# Sheet1.net
KiCad netlist of a schematic drawn in Altium Designer
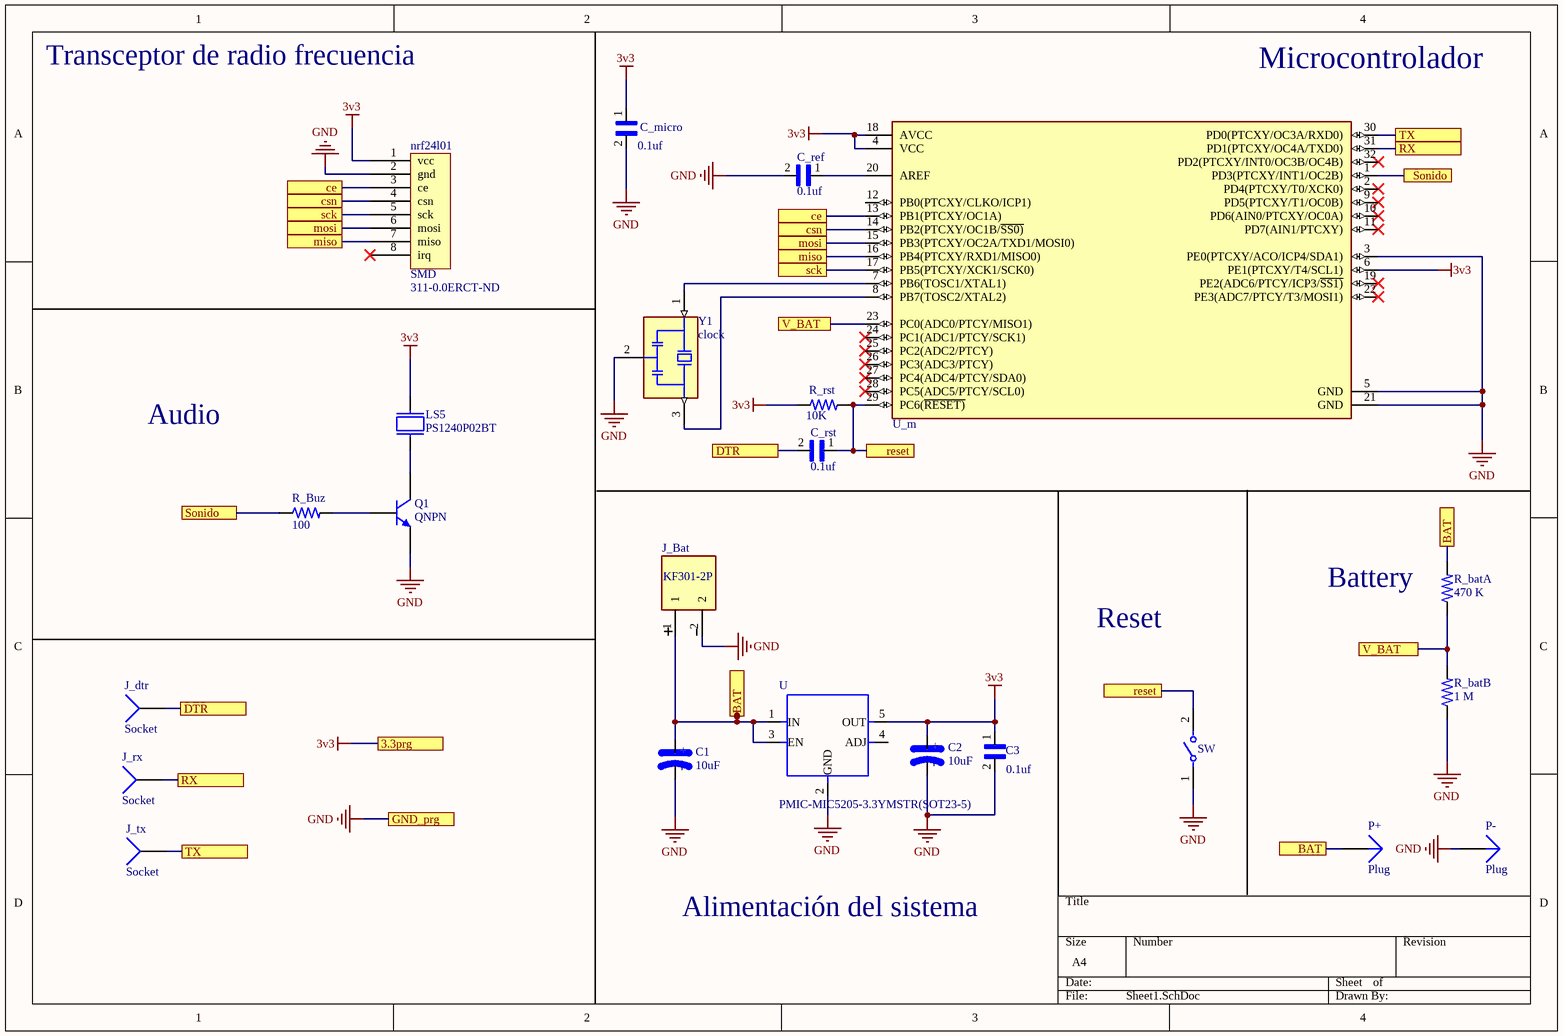
[diagram p0: Sheet1.SchDoc]

(export (version "E")
  (design (tool "Eeschema 10.0.6"))
  (components
    (comp (ref "C1")
      (value "10uF")
      (footprint "CT1206")
      (description "10ÂµF Molded Tantalum Capacitors 20V 1206 _3216 Metric_ 5Ohm")
      (fields (field (name "MF") "KEMET") (field (name "MP") "T491A106M020AT"))
      (libsource (lib "1206_tantalio") (part "TANTALUM-SMD-10UF-20V-20%(1206)"))
    )
    (comp (ref "C2")
      (value "10uF")
      (footprint "CT1206")
      (description "10ÂµF Molded Tantalum Capacitors 20V 1206 _3216 Metric_ 5Ohm")
      (fields (field (name "MF") "KEMET") (field (name "MP") "T491A106M020AT"))
      (libsource (lib "1206_tantalio") (part "TANTALUM-SMD-10UF-20V-20%(1206)"))
    )
    (comp (ref "C3")
      (value "0.1uf")
      (footprint "CAPC1608X90")
      (description "0.1ÂµF Â±10% 50V Ceramic Capacitor X7R 0603 _1608 Metric_")
      (fields (field (name "DIGI-KEY_PART_NUMBER") "311-1344-1-ND") (field (name "MP") "CC0603KRX7R9BB104"))
      (libsource (lib "cap0603") (part "CC0603KRX7R9BB104"))
    )
    (comp (ref "C_micro")
      (value "0.1uf")
      (footprint "CAPC1608X90")
      (description "0.1ÂµF Â±10% 50V Ceramic Capacitor X7R 0603 _1608 Metric_")
      (fields (field (name "DIGI-KEY_PART_NUMBER") "311-1344-1-ND") (field (name "MP") "CC0603KRX7R9BB104"))
      (libsource (lib "cap0603") (part "CC0603KRX7R9BB104"))
    )
    (comp (ref "C_ref")
      (value "0.1uf")
      (footprint "CAPC1608X90")
      (description "0.1ÂµF Â±10% 50V Ceramic Capacitor X7R 0603 _1608 Metric_")
      (fields (field (name "DIGI-KEY_PART_NUMBER") "311-1344-1-ND") (field (name "MP") "CC0603KRX7R9BB104"))
      (libsource (lib "") (part "CC0603KRX7R9BB104_1"))
    )
    (comp (ref "C_rst")
      (value "0.1uf")
      (footprint "CAPC1608X90")
      (description "0.1ÂµF Â±10% 50V Ceramic Capacitor X7R 0603 _1608 Metric_")
      (fields (field (name "DIGI-KEY_PART_NUMBER") "311-1344-1-ND") (field (name "MP") "CC0603KRX7R9BB104"))
      (libsource (lib "") (part "CC0603KRX7R9BB104_1"))
    )
    (comp (ref "J_Bat")
      (value "KF301-2P")
      (footprint "HANDSON_KF301-2P")
      (description "2 Pin Terminal Block 5mm Pitch")
      (fields (field (name "MF") "Handson Technology"))
      (libsource (lib "bornera") (part "KF301-2P"))
    )
    (comp (ref "J_dtr")
      (value "Socket")
      (footprint "PIN1")
      (fields (field (name "PUBLISHER") "Altium Limited"))
      (libsource (lib "Miscellaneous Connectors") (part "Socket"))
    )
    (comp (ref "J_rx")
      (value "Socket")
      (footprint "PIN1")
      (fields (field (name "PUBLISHER") "Altium Limited"))
      (libsource (lib "Miscellaneous Connectors") (part "Socket"))
    )
    (comp (ref "J_tx")
      (value "Socket")
      (footprint "PIN1")
      (fields (field (name "PUBLISHER") "Altium Limited"))
      (libsource (lib "Miscellaneous Connectors") (part "Socket"))
    )
    (comp (ref "LS5")
      (value "PS1240P02BT")
      (footprint "XDCR_PS1240P02BT")
      (description "Buzzers Transducer, Externally Driven Piezo 3V 4kHz 60dB @ 3V, 10cm Through Hole PC Pins")
      (fields (field (name "MF") "TDK"))
      (libsource (lib "buzzerGrande") (part "PS1240P02BT"))
    )
    (comp (ref "nrf24l01")
      (value "SMD")
      (footprint "NRF24L01")
      (fields (field (name "SUPPLIER PART NUMBER 1") "311-0.0ERCT-ND"))
      (libsource (lib "Schlib1") (part "nrf24l01_smd"))
    )
    (comp (ref "P+")
      (value "Plug")
      (footprint "PIN1")
      (fields (field (name "PUBLISHER") "Altium Limited"))
      (libsource (lib "Miscellaneous Connectors") (part "Plug"))
    )
    (comp (ref "P-")
      (value "Plug")
      (footprint "PIN1")
      (fields (field (name "PUBLISHER") "Altium Limited"))
      (libsource (lib "Miscellaneous Connectors") (part "Plug"))
    )
    (comp (ref "Q1")
      (value "QNPN")
      (footprint "SOT-23B_N")
      (description "NPN Bipolar Transistor")
      (fields (field (name "PUBLISHER") "Altium Limited"))
      (libsource (lib "Miscellaneous Devices") (part "QNPN"))
    )
    (comp (ref "R_batA")
      (value "470 K")
      (footprint "RESC2012X65N")
      (description "RES 0.33 OHM 1% 1/4W 0805")
      (fields (field (name "MF") "TE Connectivity") (field (name "TOLERANCE") "1%"))
      (libsource (lib "RES0805") (part "2-2176053-0"))
    )
    (comp (ref "R_batB")
      (value "1 M")
      (footprint "RESC2012X65N")
      (description "RES 0.33 OHM 1% 1/4W 0805")
      (fields (field (name "MF") "TE Connectivity") (field (name "TOLERANCE") "1%"))
      (libsource (lib "RES0805") (part "2-2176053-0"))
    )
    (comp (ref "R_Buz")
      (value "100")
      (footprint "RESC2012X65N")
      (description "RES 0.33 OHM 1% 1/4W 0805")
      (fields (field (name "MF") "TE Connectivity") (field (name "TOLERANCE") "1%"))
      (libsource (lib "RES0805") (part "2-2176053-0"))
    )
    (comp (ref "R_rst")
      (value "10K")
      (footprint "RES0603:RESC1608X50N")
      (description "Res, Thin Film, 13r, 0.1%, 0.1w, 0603")
      (fields (field (name "MP") "RP73D1J13RBTDG") (field (name "MF") "TE Connectivity"))
      (libsource (lib "RES0603") (part "RP73D1J13RBTDG"))
    )
    (comp (ref "SW")
      (value "B3U-1000P-B")
      (footprint "Omron_0_MFG")
      (libsource (lib "Switch_Omron_B3U-1000P-B_eec") (part "B3U-1000P-B"))
    )
    (comp (ref "U")
      (value "PMIC-MIC5205-3.3YMSTR(SOT23-5)")
      (footprint "SOT-23-5")
      (description "Linear Voltage Regulator IC 1 Output 150mA SOT-23-5")
      (fields (field (name "MP") "MIC5205-3.3YM5-TR") (field (name "MF") "Microchip"))
      (libsource (lib "3.3mini") (part "PMIC-MIC5205-3.3YMSTR(SOT23-5)"))
    )
    (comp (ref "U_m")
      (value "ATMEGA328PB-AUR")
      (footprint "Microchip_C04-074_IPC_C")
      (libsource (lib "IC_Microchip_ATMEGA328PB-AUR_eec") (part "ATMEGA328PB-AUR"))
    )
    (comp (ref "Y1")
      (value "clock")
      (footprint "OSC_CSTCE8M00G52-R0")
      (description "8MHz Ceramic Resonator Built in Capacitor 10pF Â±0.2% -20Â°C ~ 80Â°C Surface Mount")
      (fields (field (name "MF") "Murata") (field (name "MP") "CSTCE8M00G52-R0"))
      (libsource (lib "CSTCE8M00G52-R0") (part "CSTCE8M00G52-R0"))
    )
  )
  (nets
    (net (code "1") (name "/BAT") (class "Default")
      (node (ref "C1") (pin "POS") (pinfunction "POS_POS") (pintype "passive"))
      (node (ref "J_Bat") (pin "1") (pinfunction "1_1") (pintype "passive"))
      (node (ref "P+") (pin "1") (pinfunction "1_1") (pintype "passive"))
      (node (ref "R_batA") (pin "2") (pinfunction "2_2") (pintype "passive"))
      (node (ref "U") (pin "1") (pinfunction "IN_1") (pintype "bidirectional"))
      (node (ref "U") (pin "3") (pinfunction "EN_3") (pintype "bidirectional"))
    )
    (net (code "2") (name "/DTR") (class "Default")
      (node (ref "C_rst") (pin "2") (pinfunction "2_2") (pintype "passive"))
      (node (ref "J_dtr") (pin "1") (pinfunction "1_1") (pintype "passive"))
    )
    (net (code "3") (name "/RX") (class "Default")
      (node (ref "J_rx") (pin "1") (pinfunction "1_1") (pintype "passive"))
      (node (ref "U_m") (pin "31") (pinfunction "PD1(PTCXY/OC4A/TXD0)_31") (pintype "bidirectional"))
    )
    (net (code "4") (name "/Sonido") (class "Default")
      (node (ref "R_Buz") (pin "1") (pinfunction "1_1") (pintype "passive"))
      (node (ref "U_m") (pin "1") (pinfunction "PD3(PTCXY/INT1/OC2B)_1") (pintype "bidirectional"))
    )
    (net (code "5") (name "/TX") (class "Default")
      (node (ref "J_tx") (pin "1") (pinfunction "1_1") (pintype "passive"))
      (node (ref "U_m") (pin "30") (pinfunction "PD0(PTCXY/OC3A/RXD0)_30") (pintype "bidirectional"))
    )
    (net (code "6") (name "/V_BAT") (class "Default")
      (node (ref "R_batA") (pin "1") (pinfunction "1_1") (pintype "passive"))
      (node (ref "R_batB") (pin "2") (pinfunction "2_2") (pintype "passive"))
      (node (ref "U_m") (pin "23") (pinfunction "PC0(ADC0/PTCY/MISO1)_23") (pintype "bidirectional"))
    )
    (net (code "7") (name "/ce") (class "Default")
      (node (ref "U_m") (pin "13") (pinfunction "PB1(PTCXY/OC1A)_13") (pintype "bidirectional"))
      (node (ref "nrf24l01") (pin "3") (pinfunction "ce_3") (pintype "passive"))
    )
    (net (code "8") (name "/csn") (class "Default")
      (node (ref "U_m") (pin "14") (pinfunction "PB2(PTCXY/OC1B/~{SS0)}_14") (pintype "bidirectional"))
      (node (ref "nrf24l01") (pin "4") (pinfunction "csn_4") (pintype "passive"))
    )
    (net (code "9") (name "/miso") (class "Default")
      (node (ref "U_m") (pin "16") (pinfunction "PB4(PTCXY/RXD1/MISO0)_16") (pintype "bidirectional"))
      (node (ref "nrf24l01") (pin "7") (pinfunction "miso_7") (pintype "passive"))
    )
    (net (code "10") (name "/mosi") (class "Default")
      (node (ref "U_m") (pin "15") (pinfunction "PB3(PTCXY/OC2A/TXD1/MOSI0)_15") (pintype "bidirectional"))
      (node (ref "nrf24l01") (pin "6") (pinfunction "mosi_6") (pintype "passive"))
    )
    (net (code "11") (name "/reset") (class "Default")
      (node (ref "C_rst") (pin "1") (pinfunction "1_1") (pintype "passive"))
      (node (ref "R_rst") (pin "2") (pinfunction "2_2") (pintype "passive"))
      (node (ref "SW") (pin "2") (pinfunction "2_2") (pintype "passive"))
      (node (ref "U_m") (pin "29") (pinfunction "PC6(~{RESET)}_29") (pintype "bidirectional"))
    )
    (net (code "12") (name "/sck") (class "Default")
      (node (ref "U_m") (pin "17") (pinfunction "PB5(PTCXY/XCK1/SCK0)_17") (pintype "bidirectional"))
      (node (ref "nrf24l01") (pin "5") (pinfunction "sck_5") (pintype "passive"))
    )
    (net (code "13") (name "3v3") (class "Default")
      (node (ref "C2") (pin "POS") (pinfunction "POS_POS") (pintype "passive"))
      (node (ref "C3") (pin "1") (pinfunction "1_1") (pintype "passive"))
      (node (ref "C_micro") (pin "1") (pinfunction "1_1") (pintype "passive"))
      (node (ref "LS5") (pin "1") (pinfunction "1_1") (pintype "passive"))
      (node (ref "R_rst") (pin "1") (pinfunction "1_1") (pintype "passive"))
      (node (ref "U") (pin "5") (pinfunction "OUT_5") (pintype "bidirectional"))
      (node (ref "U_m") (pin "18") (pinfunction "AVCC_18") (pintype "power_in"))
      (node (ref "U_m") (pin "4") (pinfunction "VCC_4") (pintype "power_in"))
      (node (ref "U_m") (pin "6") (pinfunction "PE1(PTCXY/T4/SCL1)_6") (pintype "bidirectional"))
      (node (ref "nrf24l01") (pin "1") (pinfunction "vcc_1") (pintype "passive"))
    )
    (net (code "14") (name "GND") (class "Default")
      (node (ref "C1") (pin "NEG") (pinfunction "NEG_NEG") (pintype "passive"))
      (node (ref "C2") (pin "NEG") (pinfunction "NEG_NEG") (pintype "passive"))
      (node (ref "C3") (pin "2") (pinfunction "2_2") (pintype "passive"))
      (node (ref "C_micro") (pin "2") (pinfunction "2_2") (pintype "passive"))
      (node (ref "C_ref") (pin "2") (pinfunction "2_2") (pintype "passive"))
      (node (ref "J_Bat") (pin "2") (pinfunction "2_2") (pintype "passive"))
      (node (ref "P-") (pin "1") (pinfunction "1_1") (pintype "passive"))
      (node (ref "Q1") (pin "3") (pinfunction "E_3") (pintype "passive"))
      (node (ref "R_batB") (pin "1") (pinfunction "1_1") (pintype "passive"))
      (node (ref "SW") (pin "1") (pinfunction "1_1") (pintype "passive"))
      (node (ref "U") (pin "2") (pinfunction "GND_2") (pintype "bidirectional"))
      (node (ref "U_m") (pin "21") (pinfunction "GND_21") (pintype "power_in"))
      (node (ref "U_m") (pin "3") (pinfunction "PE0(PTCXY/ACO/ICP4/SDA1)_3") (pintype "bidirectional"))
      (node (ref "U_m") (pin "5") (pinfunction "GND_5") (pintype "power_in"))
      (node (ref "Y1") (pin "2") (pinfunction "GND_2") (pintype "power_in"))
      (node (ref "nrf24l01") (pin "2") (pinfunction "gnd_2") (pintype "passive"))
    )
    (net (code "15") (name "Net-(Q1-B)") (class "Default")
      (node (ref "Q1") (pin "2") (pinfunction "B_2") (pintype "passive"))
      (node (ref "R_Buz") (pin "2") (pinfunction "2_2") (pintype "passive"))
    )
    (net (code "16") (name "Net-(Q1-C)") (class "Default")
      (node (ref "LS5") (pin "2") (pinfunction "2_2") (pintype "passive"))
      (node (ref "Q1") (pin "1") (pinfunction "C_1") (pintype "passive"))
    )
    (net (code "17") (name "Net-(U_m-AREF)") (class "Default")
      (node (ref "C_ref") (pin "1") (pinfunction "1_1") (pintype "passive"))
      (node (ref "U_m") (pin "20") (pinfunction "AREF_20") (pintype "power_in"))
    )
    (net (code "18") (name "Net-(U_m-PB6(TOSC1{slash}XTAL1))") (class "Default")
      (node (ref "U_m") (pin "7") (pinfunction "PB6(TOSC1/XTAL1)_7") (pintype "bidirectional"))
      (node (ref "Y1") (pin "1") (pinfunction "IN_1") (pintype "input"))
    )
    (net (code "19") (name "Net-(U_m-PB7(TOSC2{slash}XTAL2))") (class "Default")
      (node (ref "U_m") (pin "8") (pinfunction "PB7(TOSC2/XTAL2)_8") (pintype "bidirectional"))
      (node (ref "Y1") (pin "3") (pinfunction "OUT_3") (pintype "output"))
    )
    (net (code "20") (name "unconnected-(U-ADJ-Pad4)") (class "Default")
      (node (ref "U") (pin "4") (pinfunction "ADJ_4") (pintype "bidirectional"))
    )
    (net (code "21") (name "unconnected-(U_m-PB0(PTCXY{slash}CLKO{slash}ICP1)-Pad12)") (class "Default")
      (node (ref "U_m") (pin "12") (pinfunction "PB0(PTCXY/CLKO/ICP1)_12") (pintype "bidirectional"))
    )
    (net (code "22") (name "unconnected-(U_m-PC1(ADC1{slash}PTCY{slash}SCK1)-Pad24)") (class "Default")
      (node (ref "U_m") (pin "24") (pinfunction "PC1(ADC1/PTCY/SCK1)_24") (pintype "bidirectional+no_connect"))
    )
    (net (code "23") (name "unconnected-(U_m-PC2(ADC2{slash}PTCY)-Pad25)") (class "Default")
      (node (ref "U_m") (pin "25") (pinfunction "PC2(ADC2/PTCY)_25") (pintype "bidirectional+no_connect"))
    )
    (net (code "24") (name "unconnected-(U_m-PC3(ADC3{slash}PTCY)-Pad26)") (class "Default")
      (node (ref "U_m") (pin "26") (pinfunction "PC3(ADC3/PTCY)_26") (pintype "bidirectional+no_connect"))
    )
    (net (code "25") (name "unconnected-(U_m-PC4(ADC4{slash}PTCY{slash}SDA0)-Pad27)") (class "Default")
      (node (ref "U_m") (pin "27") (pinfunction "PC4(ADC4/PTCY/SDA0)_27") (pintype "bidirectional+no_connect"))
    )
    (net (code "26") (name "unconnected-(U_m-PC5(ADC5{slash}PTCY{slash}SCL0)-Pad28)") (class "Default")
      (node (ref "U_m") (pin "28") (pinfunction "PC5(ADC5/PTCY/SCL0)_28") (pintype "bidirectional+no_connect"))
    )
    (net (code "27") (name "unconnected-(U_m-PD2(PTCXY{slash}INT0{slash}OC3B{slash}OC4B)-Pad32)") (class "Default")
      (node (ref "U_m") (pin "32") (pinfunction "PD2(PTCXY/INT0/OC3B/OC4B)_32") (pintype "bidirectional+no_connect"))
    )
    (net (code "28") (name "unconnected-(U_m-PD4(PTCXY{slash}T0{slash}XCK0)-Pad2)") (class "Default")
      (node (ref "U_m") (pin "2") (pinfunction "PD4(PTCXY/T0/XCK0)_2") (pintype "bidirectional+no_connect"))
    )
    (net (code "29") (name "unconnected-(U_m-PD5(PTCXY{slash}T1{slash}OC0B)-Pad9)") (class "Default")
      (node (ref "U_m") (pin "9") (pinfunction "PD5(PTCXY/T1/OC0B)_9") (pintype "bidirectional+no_connect"))
    )
    (net (code "30") (name "unconnected-(U_m-PD6(AIN0{slash}PTCXY{slash}OC0A)-Pad10)") (class "Default")
      (node (ref "U_m") (pin "10") (pinfunction "PD6(AIN0/PTCXY/OC0A)_10") (pintype "bidirectional+no_connect"))
    )
    (net (code "31") (name "unconnected-(U_m-PD7(AIN1{slash}PTCXY)-Pad11)") (class "Default")
      (node (ref "U_m") (pin "11") (pinfunction "PD7(AIN1/PTCXY)_11") (pintype "bidirectional+no_connect"))
    )
    (net (code "32") (name "unconnected-(U_m-PE2(ADC6{slash}PTCY{slash}ICP3{slash}~{SS1)}-Pad19)") (class "Default")
      (node (ref "U_m") (pin "19") (pinfunction "PE2(ADC6/PTCY/ICP3/~{SS1)}_19") (pintype "bidirectional+no_connect"))
    )
    (net (code "33") (name "unconnected-(U_m-PE3(ADC7{slash}PTCY{slash}T3{slash}MOSI1)-Pad22)") (class "Default")
      (node (ref "U_m") (pin "22") (pinfunction "PE3(ADC7/PTCY/T3/MOSI1)_22") (pintype "bidirectional+no_connect"))
    )
    (net (code "34") (name "unconnected-(nrf24l01-irq-Pad8)") (class "Default")
      (node (ref "nrf24l01") (pin "8") (pinfunction "irq_8") (pintype "passive+no_connect"))
    )
  )
)
